# Power.net
KiCad netlist of a schematic drawn in Altium Designer
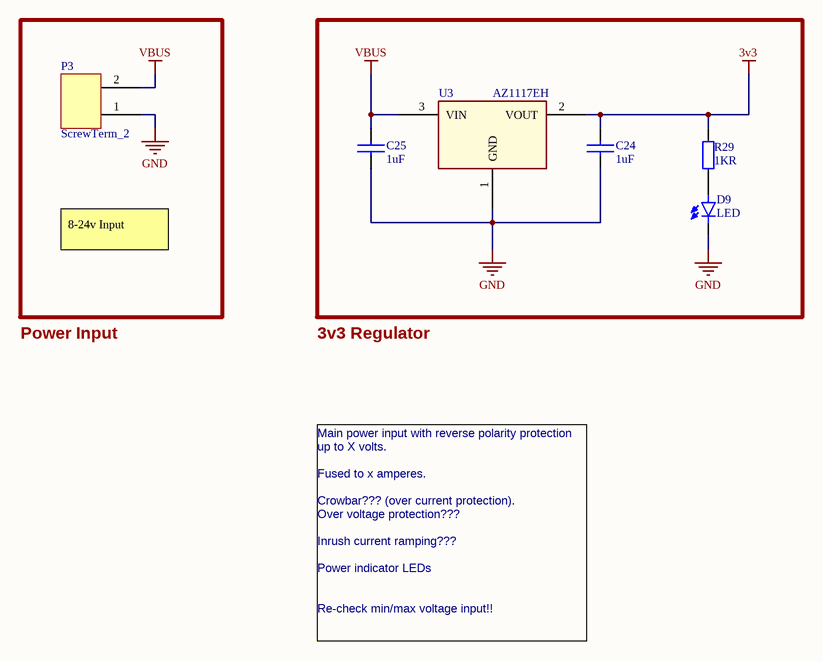
[diagram p0: Power.SchDoc]

(export (version "E")
  (design (tool "Eeschema 10.0.6"))
  (components
    (comp (ref "C24")
      (value "1uF")
      (footprint "RESC0603(1608)_N")
      (description "Non polarized capacitor")
      (libsource (lib "myPassives") (part "Capacitor"))
    )
    (comp (ref "C25")
      (value "1uF")
      (footprint "RESC0603(1608)_N")
      (description "Non polarized capacitor")
      (libsource (lib "myPassives") (part "Capacitor"))
    )
    (comp (ref "D9") (value "LED") (footprint "0603") (libsource (lib "myPassives") (part "LED")))
    (comp (ref "P3")
      (value "ScrewTerm_2")
      (footprint "ScrewTerm_2")
      (libsource (lib "Seeed") (part "ScrewTerm_2"))
    )
    (comp (ref "R29")
      (value "1KR")
      (footprint "RESC0603(1608)_N")
      (description "Resistor")
      (libsource (lib "myPassives") (part "Resistor"))
    )
    (comp (ref "U3")
      (value "AZ1117EH")
      (footprint "SOT-223")
      (fields
        (field (name "MANUFACTURER") "Diodes Incorporated")
        (field (name "PARTNUMBER") "AZ1117EH-3.3TRG1")
        (field (name "DIGIKEY PART NUMBER") "AZ1117EH-3.3TRG1DICT-ND")
      )
      (libsource (lib "myLibs") (part "AZ1117EH"))
    )
  )
  (nets
    (net (code "1") (name "3v3") (class "Default")
      (node (ref "C24") (pin "1") (pintype "passive"))
      (node (ref "R29") (pin "1") (pintype "passive"))
      (node (ref "U3") (pin "2") (pinfunction "VOUT_2") (pintype "passive"))
    )
    (net (code "2") (name "GND") (class "Default")
      (node (ref "C24") (pin "2") (pintype "passive"))
      (node (ref "C25") (pin "2") (pintype "passive"))
      (node (ref "D9") (pin "1") (pintype "passive"))
      (node (ref "P3") (pin "1") (pintype "passive"))
      (node (ref "U3") (pin "1") (pinfunction "GND_1") (pintype "passive"))
    )
    (net (code "3") (name "Net-(D9-Pad2)") (class "Default")
      (node (ref "D9") (pin "2") (pintype "passive"))
      (node (ref "R29") (pin "2") (pintype "passive"))
    )
    (net (code "4") (name "VBUS") (class "Default")
      (node (ref "C25") (pin "1") (pintype "passive"))
      (node (ref "P3") (pin "2") (pintype "passive"))
      (node (ref "U3") (pin "3") (pinfunction "VIN_3") (pintype "passive"))
    )
  )
)
